# Sheet1.net
KiCad netlist of a schematic drawn in Altium Designer
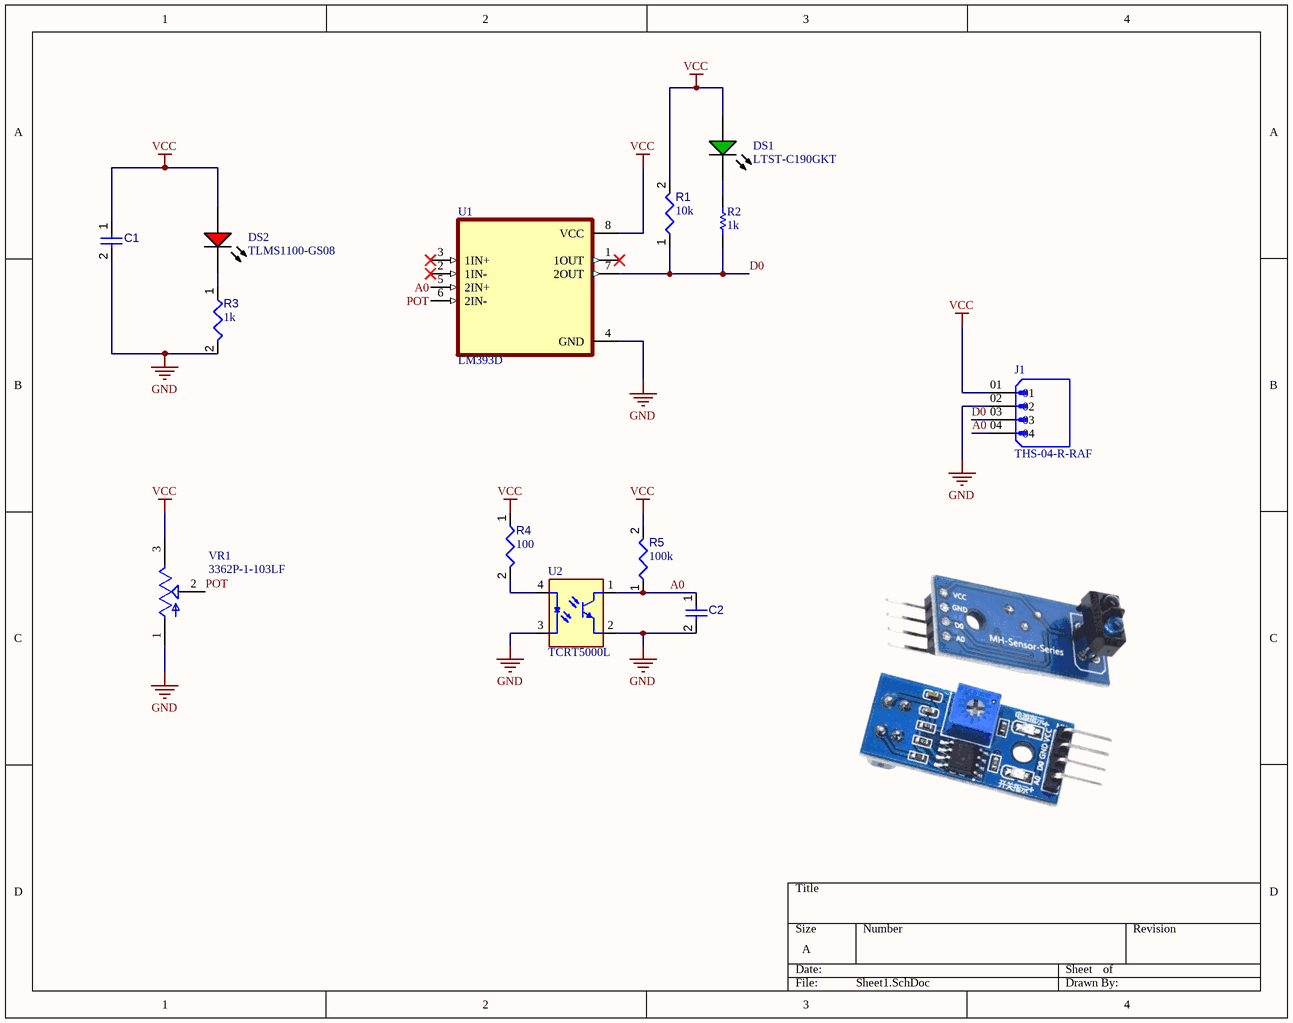
[diagram p0: Sheet1.SchDoc]

(export (version "E")
  (design (tool "Eeschema 10.0.6"))
  (components
    (comp (ref "C1")
      (value "Capacitor 1 uF +/- 10% 25 V 0805")
      (footprint "CAPC2013X145X50ML20T25")
      (description "Chip Capacitor, 1 uF, +/-10%, 25 V, 0805 (2012 Metric)")
      (fields (field (name "TOLERANCE") "10%"))
      (libsource (lib "Med khalil khlifi") (part "CAP-NP-2"))
    )
    (comp (ref "C2")
      (value "Capacitor 1 uF +/- 10% 25 V 0805")
      (footprint "CAPC2013X145X50ML20T25")
      (description "Chip Capacitor, 1 uF, +/-10%, 25 V, 0805 (2012 Metric)")
      (fields (field (name "TOLERANCE") "10%"))
      (libsource (lib "Med khalil khlifi") (part "CAP-NP-2"))
    )
    (comp (ref "DS1")
      (value "LTST-C190GKT")
      (footprint "LTST-C190GKT_V")
      (description "LED Uni-Color Green, 100 mW, 30 mA, -55 to 85 degC, 2-Pin SMD, RoHS, Tape and Reel")
      (fields (field (name "POWER") "100mW") (field (name "MANUFACTURER") "Lite-On"))
      (libsource (lib "Med khalil khlifi") (part "LED-GREEN-AK-2"))
    )
    (comp (ref "DS2")
      (value "TLMS1100-GS08")
      (footprint "VISH-TLMX1100_V")
      (description "Red Led, 20mA, 2.1 V, -40 to 100 degC, 2-Pin SMD (0603), RoHS, Tape and Reel")
      (fields (field (name "MANUFACTURER") "Vishay Semiconductor") (field (name "POWER") "90mW"))
      (libsource (lib "Med khalil khlifi") (part "LED-RED-AK-2"))
    )
    (comp (ref "J1")
      (value "THS-04-R-RAF")
      (footprint "VALCON_THS-04-R-RAF")
      (libsource (lib "Header 4") (part "THS-04-R-RAF"))
    )
    (comp (ref "R1")
      (value "10k")
      (footprint "RESC1608X55X25ML10T15")
      (description "Chip Resistor, 10 KOhm, +/- 1%, 01 W, -55 to 155 degC, 0603 (1608 Metric)")
      (fields (field (name "POWER") "100mW") (field (name "TOLERANCE") "1%"))
      (libsource (lib "Med khalil khlifi") (part "RES-2"))
    )
    (comp (ref "R2")
      (value "1k")
      (footprint "RESC1005X40X25ML05T05")
      (description "Chip Resistor, 1 KOhm, +/- 1%, 0.1 W, -55 to 155 degC, 0402 (1005 Metric)")
      (fields (field (name "POWER") "100mW") (field (name "TOLERANCE") "1%"))
      (libsource (lib "") (part "RES-2_1"))
    )
    (comp (ref "R3")
      (value "1k")
      (footprint "RESC0402(1005)_L")
      (description "Chip Resistor, 1 kOhms, +/-5 %, 63 mW, -55 to 155 degC, 0402")
      (fields (field (name "TOLERANCE") "5%") (field (name "POWER") "63mW"))
      (libsource (lib "Med khalil khlifi") (part "RES-2"))
    )
    (comp (ref "R4")
      (value "100")
      (footprint "RESC0402(1005)_L")
      (description "Chip Resistor, 100 Ohms, +/-1 %, 63 mW, -55 to 155 degC, 0402")
      (fields (field (name "POWER") "63mW") (field (name "TOLERANCE") "1%"))
      (libsource (lib "Med khalil khlifi") (part "RES-2"))
    )
    (comp (ref "R5")
      (value "100k")
      (footprint "RESC1005X40X25ML05T05")
      (description "Chip Resistor, 100 KOhm, +/- 1%, 0.063 W, -55 to 155 degC, 0402 (1005 Metric)")
      (fields (field (name "TOLERANCE") "1%") (field (name "POWER") "63mW"))
      (libsource (lib "Med khalil khlifi") (part "RES-2"))
    )
    (comp (ref "U1")
      (value "LM393D")
      (footprint "SOIC127P599X175-8N")
      (description "Dual differential comparator, commercial grade")
      (fields (field (name "MF") "Texas Instruments"))
      (libsource (lib "LM393D") (part "LM393D"))
    )
    (comp (ref "U2")
      (value "TCRT5000L")
      (footprint "XDCR_TCRT5000L")
      (description "Reflective Optical Sensor 0.591 _15mm_ PCB Mount")
      (fields (field (name "MF") "Vishay"))
      (libsource (lib "TCRT5000L") (part "TCRT5000L"))
    )
    (comp (ref "VR1")
      (value "3362P-1-103LF")
      (footprint "TRIM_3362P-1-103LF")
      (description "10 kOhms 0.5W, 1/2W PC Pins Through Hole Trimmer Potentiometer Cermet 1 Turn Top Adjustment")
      (fields (field (name "DIGI-KEY_PART_NUMBER") "3362P-103LF-ND") (field (name "MF") "Bourns"))
      (libsource (lib "Potentiometer") (part "3362P-1-103LF"))
    )
  )
  (nets
    (net (code "1") (name "/A0") (class "Default")
      (node (ref "C2") (pin "1") (pinfunction "1_1") (pintype "passive"))
      (node (ref "J1") (pin "04") (pinfunction "04_04") (pintype "passive"))
      (node (ref "R5") (pin "1") (pinfunction "1_1") (pintype "passive"))
      (node (ref "U1") (pin "5") (pinfunction "2IN+_5") (pintype "input"))
      (node (ref "U2") (pin "1") (pinfunction "CO_1") (pintype "passive"))
    )
    (net (code "2") (name "/D0") (class "Default")
      (node (ref "J1") (pin "03") (pinfunction "03_03") (pintype "passive"))
      (node (ref "R1") (pin "1") (pinfunction "1_1") (pintype "passive"))
      (node (ref "R2") (pin "1") (pinfunction "1_1") (pintype "passive"))
      (node (ref "U1") (pin "7") (pinfunction "2OUT_7") (pintype "output"))
    )
    (net (code "3") (name "/POT") (class "Default")
      (node (ref "U1") (pin "6") (pinfunction "2IN-_6") (pintype "input"))
      (node (ref "VR1") (pin "2") (pinfunction "WIPER_2") (pintype "passive"))
    )
    (net (code "4") (name "GND") (class "Default")
      (node (ref "C1") (pin "2") (pinfunction "2_2") (pintype "passive"))
      (node (ref "C2") (pin "2") (pinfunction "2_2") (pintype "passive"))
      (node (ref "J1") (pin "02") (pinfunction "02_02") (pintype "passive"))
      (node (ref "R3") (pin "2") (pinfunction "2_2") (pintype "passive"))
      (node (ref "U1") (pin "4") (pinfunction "GND_4") (pintype "power_in"))
      (node (ref "U2") (pin "2") (pinfunction "E_2") (pintype "passive"))
      (node (ref "U2") (pin "3") (pinfunction "C_3") (pintype "passive"))
      (node (ref "VR1") (pin "1") (pinfunction "CCW_1") (pintype "passive"))
    )
    (net (code "5") (name "Net-(DS1-K)") (class "Default")
      (node (ref "DS1") (pin "2") (pinfunction "K_2") (pintype "passive"))
      (node (ref "R2") (pin "2") (pinfunction "2_2") (pintype "passive"))
    )
    (net (code "6") (name "Net-(DS2-K)") (class "Default")
      (node (ref "DS2") (pin "2") (pinfunction "K_2") (pintype "passive"))
      (node (ref "R3") (pin "1") (pinfunction "1_1") (pintype "passive"))
    )
    (net (code "7") (name "Net-(U2-A)") (class "Default")
      (node (ref "R4") (pin "2") (pinfunction "2_2") (pintype "passive"))
      (node (ref "U2") (pin "4") (pinfunction "A_4") (pintype "passive"))
    )
    (net (code "8") (name "VCC") (class "Default")
      (node (ref "C1") (pin "1") (pinfunction "1_1") (pintype "passive"))
      (node (ref "DS1") (pin "1") (pinfunction "A_1") (pintype "passive"))
      (node (ref "DS2") (pin "1") (pinfunction "A_1") (pintype "passive"))
      (node (ref "J1") (pin "01") (pinfunction "01_01") (pintype "passive"))
      (node (ref "R1") (pin "2") (pinfunction "2_2") (pintype "passive"))
      (node (ref "R4") (pin "1") (pinfunction "1_1") (pintype "passive"))
      (node (ref "R5") (pin "2") (pinfunction "2_2") (pintype "passive"))
      (node (ref "U1") (pin "8") (pinfunction "VCC_8") (pintype "power_in"))
      (node (ref "VR1") (pin "3") (pinfunction "CW_3") (pintype "passive"))
    )
    (net (code "9") (name "unconnected-(U1-1IN+-Pad3)") (class "Default")
      (node (ref "U1") (pin "3") (pinfunction "1IN+_3") (pintype "input+no_connect"))
    )
    (net (code "10") (name "unconnected-(U1-1IN--Pad2)") (class "Default")
      (node (ref "U1") (pin "2") (pinfunction "1IN-_2") (pintype "input+no_connect"))
    )
    (net (code "11") (name "unconnected-(U1-1OUT-Pad1)") (class "Default")
      (node (ref "U1") (pin "1") (pinfunction "1OUT_1") (pintype "output+no_connect"))
    )
  )
)
